# Sheet5.net
KiCad netlist of a schematic drawn in Altium Designer
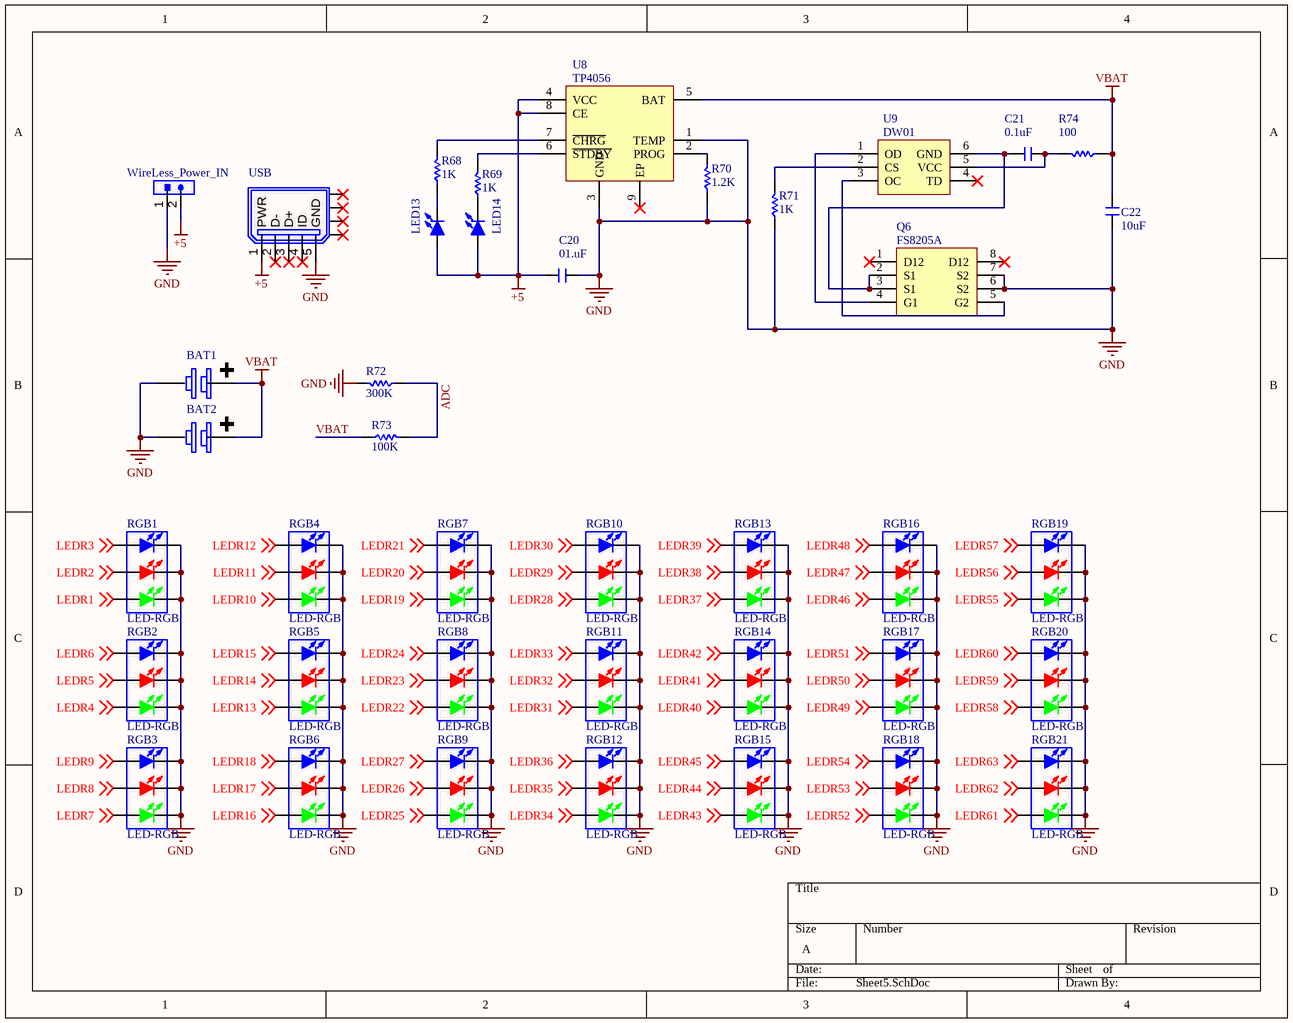
[diagram p0: Sheet5.SchDoc]

(export (version "E")
  (design (tool "Eeschema 10.0.6"))
  (components
    (comp (ref "BAT1")
      (value "Battery 1850")
      (footprint "18650 SINGLE 2")
      (libsource (lib "Battery Holder") (part "Battery 1850"))
    )
    (comp (ref "BAT2")
      (value "Battery 1850")
      (footprint "18650 SINGLE 2")
      (libsource (lib "Battery Holder") (part "Battery 1850"))
    )
    (comp (ref "C20")
      (value "01.uF")
      (footprint "C 0402")
      (description "Non-polar patch capacitor")
      (fields (field (name "版权归属") "源创客"))
      (libsource (lib "Passive (Resistor-Capacitor-Inductor-Veristor-Ferrite)") (part "C"))
    )
    (comp (ref "C21")
      (value "0.1uF")
      (footprint "C 0402")
      (description "Non-polar patch capacitor")
      (fields (field (name "版权归属") "源创客"))
      (libsource (lib "Passive (Resistor-Capacitor-Inductor-Veristor-Ferrite)") (part "C"))
    )
    (comp (ref "C22")
      (value "10uF")
      (footprint "C 0603")
      (description "Non-polar patch capacitor")
      (fields (field (name "版权归属") "源创客"))
      (libsource (lib "Passive (Resistor-Capacitor-Inductor-Veristor-Ferrite)") (part "C"))
    )
    (comp (ref "LED13")
      (value "LED-SMD")
      (footprint "LED 0805R")
      (description "Patch LED")
      (fields (field (name "版权归属") "源创客"))
      (libsource (lib "LED") (part "LED-SMD"))
    )
    (comp (ref "LED14")
      (value "LED-SMD")
      (footprint "LED 0805G")
      (description "Patch LED")
      (fields (field (name "版权归属") "源创客"))
      (libsource (lib "LED") (part "LED-SMD"))
    )
    (comp (ref "Q6")
      (value "FS8205A")
      (footprint "SSOP8_L")
      (description "Dual N-Channel Enhancement Mode Power MOSFET")
      (libsource (lib "Integrated Circuit") (part "FS8205A"))
    )
    (comp (ref "R68")
      (value "1K")
      (footprint "R 0402")
      (description "Chip resistor")
      (fields (field (name "版权归属") "源创客"))
      (libsource (lib "Passive (Resistor-Capacitor-Inductor-Veristor-Ferrite)") (part "R"))
    )
    (comp (ref "R69")
      (value "1K")
      (footprint "R 0402")
      (description "Chip resistor")
      (fields (field (name "版权归属") "源创客"))
      (libsource (lib "Passive (Resistor-Capacitor-Inductor-Veristor-Ferrite)") (part "R"))
    )
    (comp (ref "R70")
      (value "1.2K")
      (footprint "R 0402")
      (description "Chip resistor")
      (fields (field (name "版权归属") "源创客"))
      (libsource (lib "Passive (Resistor-Capacitor-Inductor-Veristor-Ferrite)") (part "R"))
    )
    (comp (ref "R71")
      (value "1K")
      (footprint "R 0402")
      (description "Chip resistor")
      (fields (field (name "版权归属") "源创客"))
      (libsource (lib "Passive (Resistor-Capacitor-Inductor-Veristor-Ferrite)") (part "R"))
    )
    (comp (ref "R72")
      (value "300K")
      (footprint "R 0805")
      (description "Chip resistor")
      (fields (field (name "版权归属") "源创客"))
      (libsource (lib "Passive (Resistor-Capacitor-Inductor-Veristor-Ferrite)") (part "R"))
    )
    (comp (ref "R73")
      (value "100K")
      (footprint "R 0805")
      (description "Chip resistor")
      (fields (field (name "版权归属") "源创客"))
      (libsource (lib "Passive (Resistor-Capacitor-Inductor-Veristor-Ferrite)") (part "R"))
    )
    (comp (ref "R74")
      (value "100")
      (footprint "R 0402")
      (description "Chip resistor")
      (fields (field (name "版权归属") "源创客"))
      (libsource (lib "Passive (Resistor-Capacitor-Inductor-Veristor-Ferrite)") (part "R"))
    )
    (comp (ref "RGB1")
      (value "LED-RGB")
      (footprint "LED 5050")
      (description "Three primary color LED")
      (fields (field (name "版权归属") "源创客"))
      (libsource (lib "LED") (part "LED-RGB"))
    )
    (comp (ref "RGB2")
      (value "LED-RGB")
      (footprint "LED 5050")
      (description "Three primary color LED")
      (fields (field (name "版权归属") "源创客"))
      (libsource (lib "LED") (part "LED-RGB"))
    )
    (comp (ref "RGB3")
      (value "LED-RGB")
      (footprint "LED 5050")
      (description "Three primary color LED")
      (fields (field (name "版权归属") "源创客"))
      (libsource (lib "LED") (part "LED-RGB"))
    )
    (comp (ref "RGB4")
      (value "LED-RGB")
      (footprint "LED 5050")
      (description "Three primary color LED")
      (fields (field (name "版权归属") "源创客"))
      (libsource (lib "LED") (part "LED-RGB"))
    )
    (comp (ref "RGB5")
      (value "LED-RGB")
      (footprint "LED 5050")
      (description "Three primary color LED")
      (fields (field (name "版权归属") "源创客"))
      (libsource (lib "LED") (part "LED-RGB"))
    )
    (comp (ref "RGB6")
      (value "LED-RGB")
      (footprint "LED 5050")
      (description "Three primary color LED")
      (fields (field (name "版权归属") "源创客"))
      (libsource (lib "LED") (part "LED-RGB"))
    )
    (comp (ref "RGB7")
      (value "LED-RGB")
      (footprint "LED 5050")
      (description "Three primary color LED")
      (fields (field (name "版权归属") "源创客"))
      (libsource (lib "LED") (part "LED-RGB"))
    )
    (comp (ref "RGB8")
      (value "LED-RGB")
      (footprint "LED 5050")
      (description "Three primary color LED")
      (fields (field (name "版权归属") "源创客"))
      (libsource (lib "LED") (part "LED-RGB"))
    )
    (comp (ref "RGB9")
      (value "LED-RGB")
      (footprint "LED 5050")
      (description "Three primary color LED")
      (fields (field (name "版权归属") "源创客"))
      (libsource (lib "LED") (part "LED-RGB"))
    )
    (comp (ref "RGB10")
      (value "LED-RGB")
      (footprint "LED 5050")
      (description "Three primary color LED")
      (fields (field (name "版权归属") "源创客"))
      (libsource (lib "LED") (part "LED-RGB"))
    )
    (comp (ref "RGB11")
      (value "LED-RGB")
      (footprint "LED 5050")
      (description "Three primary color LED")
      (fields (field (name "版权归属") "源创客"))
      (libsource (lib "LED") (part "LED-RGB"))
    )
    (comp (ref "RGB12")
      (value "LED-RGB")
      (footprint "LED 5050")
      (description "Three primary color LED")
      (fields (field (name "版权归属") "源创客"))
      (libsource (lib "LED") (part "LED-RGB"))
    )
    (comp (ref "RGB13")
      (value "LED-RGB")
      (footprint "LED 5050")
      (description "Three primary color LED")
      (fields (field (name "版权归属") "源创客"))
      (libsource (lib "LED") (part "LED-RGB"))
    )
    (comp (ref "RGB14")
      (value "LED-RGB")
      (footprint "LED 5050")
      (description "Three primary color LED")
      (fields (field (name "版权归属") "源创客"))
      (libsource (lib "LED") (part "LED-RGB"))
    )
    (comp (ref "RGB15")
      (value "LED-RGB")
      (footprint "LED 5050")
      (description "Three primary color LED")
      (fields (field (name "版权归属") "源创客"))
      (libsource (lib "LED") (part "LED-RGB"))
    )
    (comp (ref "RGB16")
      (value "LED-RGB")
      (footprint "LED 5050")
      (description "Three primary color LED")
      (fields (field (name "版权归属") "源创客"))
      (libsource (lib "LED") (part "LED-RGB"))
    )
    (comp (ref "RGB17")
      (value "LED-RGB")
      (footprint "LED 5050")
      (description "Three primary color LED")
      (fields (field (name "版权归属") "源创客"))
      (libsource (lib "LED") (part "LED-RGB"))
    )
    (comp (ref "RGB18")
      (value "LED-RGB")
      (footprint "LED 5050")
      (description "Three primary color LED")
      (fields (field (name "版权归属") "源创客"))
      (libsource (lib "LED") (part "LED-RGB"))
    )
    (comp (ref "RGB19")
      (value "LED-RGB")
      (footprint "LED 5050")
      (description "Three primary color LED")
      (fields (field (name "版权归属") "源创客"))
      (libsource (lib "LED") (part "LED-RGB"))
    )
    (comp (ref "RGB20")
      (value "LED-RGB")
      (footprint "LED 5050")
      (description "Three primary color LED")
      (fields (field (name "版权归属") "源创客"))
      (libsource (lib "LED") (part "LED-RGB"))
    )
    (comp (ref "RGB21")
      (value "LED-RGB")
      (footprint "LED 5050")
      (description "Three primary color LED")
      (fields (field (name "版权归属") "源创客"))
      (libsource (lib "LED") (part "LED-RGB"))
    )
    (comp (ref "U8")
      (value "TP4056")
      (footprint "SOP8_M-EP")
      (description "Lithium battery charge management")
      (fields (field (name "版权归属") "源创客"))
      (libsource (lib "Integrated Circuit") (part "TP4056"))
    )
    (comp (ref "U9")
      (value "DW01")
      (footprint "SOT23-6M")
      (description "Lithium battery overcurrent protection IC")
      (fields (field (name "版权归属") "源创客"))
      (libsource (lib "Integrated Circuit") (part "DW01"))
    )
    (comp (ref "USB")
      (value "USB-5P")
      (footprint "USB-micro_B")
      (description "Micro & Mini USB female")
      (fields (field (name "版权归属") "源创客"))
      (libsource (lib "IO (Power-USB-Serial-VGA-RJ-Audio-Buzzer)") (part "USB-5P"))
    )
    (comp (ref "WireLess_Power_IN")
      (value "HDR-1X2")
      (footprint "XH2.54-2P")
      (description "2P Connector")
      (fields (field (name "版权归属") "源创客"))
      (libsource (lib "Connectors") (part "Header 2"))
    )
  )
  (nets
    (net (code "1") (name "+5") (class "Default")
      (node (ref "C20") (pin "2") (pinfunction "2_2") (pintype "passive"))
      (node (ref "LED13") (pin "1") (pinfunction "A_1") (pintype "passive"))
      (node (ref "LED14") (pin "1") (pinfunction "A_1") (pintype "passive"))
      (node (ref "U8") (pin "4") (pinfunction "VCC_4") (pintype "passive"))
      (node (ref "U8") (pin "8") (pinfunction "CE_8") (pintype "passive"))
      (node (ref "USB") (pin "1") (pinfunction "PWR_1") (pintype "power_in"))
      (node (ref "WireLess_Power_IN") (pin "2") (pintype "passive"))
    )
    (net (code "2") (name "/ADC") (class "Default")
      (node (ref "R72") (pin "1") (pinfunction "1_1") (pintype "passive"))
      (node (ref "R73") (pin "2") (pinfunction "2_2") (pintype "passive"))
    )
    (net (code "3") (name "GND") (class "Default")
      (node (ref "BAT1") (pin "2") (pinfunction "-_2") (pintype "passive"))
      (node (ref "BAT2") (pin "2") (pinfunction "-_2") (pintype "passive"))
      (node (ref "C20") (pin "1") (pinfunction "1_1") (pintype "passive"))
      (node (ref "C22") (pin "1") (pinfunction "1_1") (pintype "passive"))
      (node (ref "Q6") (pin "6") (pinfunction "S2_6") (pintype "passive"))
      (node (ref "Q6") (pin "7") (pinfunction "S2_7") (pintype "passive"))
      (node (ref "R70") (pin "1") (pinfunction "1_1") (pintype "passive"))
      (node (ref "R71") (pin "1") (pinfunction "1_1") (pintype "passive"))
      (node (ref "R72") (pin "2") (pinfunction "2_2") (pintype "passive"))
      (node (ref "RGB1") (pin "2") (pinfunction "BULE_K_2") (pintype "passive"))
      (node (ref "RGB1") (pin "4") (pinfunction "RED_K_4") (pintype "passive"))
      (node (ref "RGB1") (pin "6") (pinfunction "GREEN_K_6") (pintype "passive"))
      (node (ref "RGB10") (pin "2") (pinfunction "BULE_K_2") (pintype "passive"))
      (node (ref "RGB10") (pin "4") (pinfunction "RED_K_4") (pintype "passive"))
      (node (ref "RGB10") (pin "6") (pinfunction "GREEN_K_6") (pintype "passive"))
      (node (ref "RGB11") (pin "2") (pinfunction "BULE_K_2") (pintype "passive"))
      (node (ref "RGB11") (pin "4") (pinfunction "RED_K_4") (pintype "passive"))
      (node (ref "RGB11") (pin "6") (pinfunction "GREEN_K_6") (pintype "passive"))
      (node (ref "RGB12") (pin "2") (pinfunction "BULE_K_2") (pintype "passive"))
      (node (ref "RGB12") (pin "4") (pinfunction "RED_K_4") (pintype "passive"))
      (node (ref "RGB12") (pin "6") (pinfunction "GREEN_K_6") (pintype "passive"))
      (node (ref "RGB13") (pin "2") (pinfunction "BULE_K_2") (pintype "passive"))
      (node (ref "RGB13") (pin "4") (pinfunction "RED_K_4") (pintype "passive"))
      (node (ref "RGB13") (pin "6") (pinfunction "GREEN_K_6") (pintype "passive"))
      (node (ref "RGB14") (pin "2") (pinfunction "BULE_K_2") (pintype "passive"))
      (node (ref "RGB14") (pin "4") (pinfunction "RED_K_4") (pintype "passive"))
      (node (ref "RGB14") (pin "6") (pinfunction "GREEN_K_6") (pintype "passive"))
      (node (ref "RGB15") (pin "2") (pinfunction "BULE_K_2") (pintype "passive"))
      (node (ref "RGB15") (pin "4") (pinfunction "RED_K_4") (pintype "passive"))
      (node (ref "RGB15") (pin "6") (pinfunction "GREEN_K_6") (pintype "passive"))
      (node (ref "RGB16") (pin "2") (pinfunction "BULE_K_2") (pintype "passive"))
      (node (ref "RGB16") (pin "4") (pinfunction "RED_K_4") (pintype "passive"))
      (node (ref "RGB16") (pin "6") (pinfunction "GREEN_K_6") (pintype "passive"))
      (node (ref "RGB17") (pin "2") (pinfunction "BULE_K_2") (pintype "passive"))
      (node (ref "RGB17") (pin "4") (pinfunction "RED_K_4") (pintype "passive"))
      (node (ref "RGB17") (pin "6") (pinfunction "GREEN_K_6") (pintype "passive"))
      (node (ref "RGB18") (pin "2") (pinfunction "BULE_K_2") (pintype "passive"))
      (node (ref "RGB18") (pin "4") (pinfunction "RED_K_4") (pintype "passive"))
      (node (ref "RGB18") (pin "6") (pinfunction "GREEN_K_6") (pintype "passive"))
      (node (ref "RGB19") (pin "2") (pinfunction "BULE_K_2") (pintype "passive"))
      (node (ref "RGB19") (pin "4") (pinfunction "RED_K_4") (pintype "passive"))
      (node (ref "RGB19") (pin "6") (pinfunction "GREEN_K_6") (pintype "passive"))
      (node (ref "RGB2") (pin "2") (pinfunction "BULE_K_2") (pintype "passive"))
      (node (ref "RGB2") (pin "4") (pinfunction "RED_K_4") (pintype "passive"))
      (node (ref "RGB2") (pin "6") (pinfunction "GREEN_K_6") (pintype "passive"))
      (node (ref "RGB20") (pin "2") (pinfunction "BULE_K_2") (pintype "passive"))
      (node (ref "RGB20") (pin "4") (pinfunction "RED_K_4") (pintype "passive"))
      (node (ref "RGB20") (pin "6") (pinfunction "GREEN_K_6") (pintype "passive"))
      (node (ref "RGB21") (pin "2") (pinfunction "BULE_K_2") (pintype "passive"))
      (node (ref "RGB21") (pin "4") (pinfunction "RED_K_4") (pintype "passive"))
      (node (ref "RGB21") (pin "6") (pinfunction "GREEN_K_6") (pintype "passive"))
      (node (ref "RGB3") (pin "2") (pinfunction "BULE_K_2") (pintype "passive"))
      (node (ref "RGB3") (pin "4") (pinfunction "RED_K_4") (pintype "passive"))
      (node (ref "RGB3") (pin "6") (pinfunction "GREEN_K_6") (pintype "passive"))
      (node (ref "RGB4") (pin "2") (pinfunction "BULE_K_2") (pintype "passive"))
      (node (ref "RGB4") (pin "4") (pinfunction "RED_K_4") (pintype "passive"))
      (node (ref "RGB4") (pin "6") (pinfunction "GREEN_K_6") (pintype "passive"))
      (node (ref "RGB5") (pin "2") (pinfunction "BULE_K_2") (pintype "passive"))
      (node (ref "RGB5") (pin "4") (pinfunction "RED_K_4") (pintype "passive"))
      (node (ref "RGB5") (pin "6") (pinfunction "GREEN_K_6") (pintype "passive"))
      (node (ref "RGB6") (pin "2") (pinfunction "BULE_K_2") (pintype "passive"))
      (node (ref "RGB6") (pin "4") (pinfunction "RED_K_4") (pintype "passive"))
      (node (ref "RGB6") (pin "6") (pinfunction "GREEN_K_6") (pintype "passive"))
      (node (ref "RGB7") (pin "2") (pinfunction "BULE_K_2") (pintype "passive"))
      (node (ref "RGB7") (pin "4") (pinfunction "RED_K_4") (pintype "passive"))
      (node (ref "RGB7") (pin "6") (pinfunction "GREEN_K_6") (pintype "passive"))
      (node (ref "RGB8") (pin "2") (pinfunction "BULE_K_2") (pintype "passive"))
      (node (ref "RGB8") (pin "4") (pinfunction "RED_K_4") (pintype "passive"))
      (node (ref "RGB8") (pin "6") (pinfunction "GREEN_K_6") (pintype "passive"))
      (node (ref "RGB9") (pin "2") (pinfunction "BULE_K_2") (pintype "passive"))
      (node (ref "RGB9") (pin "4") (pinfunction "RED_K_4") (pintype "passive"))
      (node (ref "RGB9") (pin "6") (pinfunction "GREEN_K_6") (pintype "passive"))
      (node (ref "U8") (pin "1") (pinfunction "TEMP_1") (pintype "passive"))
      (node (ref "U8") (pin "3") (pinfunction "GND_3") (pintype "passive"))
      (node (ref "USB") (pin "5") (pinfunction "GND_5") (pintype "power_in"))
      (node (ref "WireLess_Power_IN") (pin "1") (pintype "passive"))
    )
    (net (code "4") (name "LEDR1") (class "Default")
      (node (ref "RGB1") (pin "5") (pinfunction "GREEN_A_5") (pintype "passive"))
    )
    (net (code "5") (name "LEDR2") (class "Default")
      (node (ref "RGB1") (pin "3") (pinfunction "RED_A_3") (pintype "passive"))
    )
    (net (code "6") (name "LEDR3") (class "Default")
      (node (ref "RGB1") (pin "1") (pinfunction "BULE_A_1") (pintype "passive"))
    )
    (net (code "7") (name "LEDR4") (class "Default")
      (node (ref "RGB2") (pin "5") (pinfunction "GREEN_A_5") (pintype "passive"))
    )
    (net (code "8") (name "LEDR5") (class "Default")
      (node (ref "RGB2") (pin "3") (pinfunction "RED_A_3") (pintype "passive"))
    )
    (net (code "9") (name "LEDR6") (class "Default")
      (node (ref "RGB2") (pin "1") (pinfunction "BULE_A_1") (pintype "passive"))
    )
    (net (code "10") (name "LEDR7") (class "Default")
      (node (ref "RGB3") (pin "5") (pinfunction "GREEN_A_5") (pintype "passive"))
    )
    (net (code "11") (name "LEDR8") (class "Default")
      (node (ref "RGB3") (pin "3") (pinfunction "RED_A_3") (pintype "passive"))
    )
    (net (code "12") (name "LEDR9") (class "Default")
      (node (ref "RGB3") (pin "1") (pinfunction "BULE_A_1") (pintype "passive"))
    )
    (net (code "13") (name "LEDR10") (class "Default")
      (node (ref "RGB4") (pin "5") (pinfunction "GREEN_A_5") (pintype "passive"))
    )
    (net (code "14") (name "LEDR11") (class "Default")
      (node (ref "RGB4") (pin "3") (pinfunction "RED_A_3") (pintype "passive"))
    )
    (net (code "15") (name "LEDR12") (class "Default")
      (node (ref "RGB4") (pin "1") (pinfunction "BULE_A_1") (pintype "passive"))
    )
    (net (code "16") (name "LEDR13") (class "Default")
      (node (ref "RGB5") (pin "5") (pinfunction "GREEN_A_5") (pintype "passive"))
    )
    (net (code "17") (name "LEDR14") (class "Default")
      (node (ref "RGB5") (pin "3") (pinfunction "RED_A_3") (pintype "passive"))
    )
    (net (code "18") (name "LEDR15") (class "Default")
      (node (ref "RGB5") (pin "1") (pinfunction "BULE_A_1") (pintype "passive"))
    )
    (net (code "19") (name "LEDR16") (class "Default")
      (node (ref "RGB6") (pin "5") (pinfunction "GREEN_A_5") (pintype "passive"))
    )
    (net (code "20") (name "LEDR17") (class "Default")
      (node (ref "RGB6") (pin "3") (pinfunction "RED_A_3") (pintype "passive"))
    )
    (net (code "21") (name "LEDR18") (class "Default")
      (node (ref "RGB6") (pin "1") (pinfunction "BULE_A_1") (pintype "passive"))
    )
    (net (code "22") (name "LEDR19") (class "Default")
      (node (ref "RGB7") (pin "5") (pinfunction "GREEN_A_5") (pintype "passive"))
    )
    (net (code "23") (name "LEDR20") (class "Default")
      (node (ref "RGB7") (pin "3") (pinfunction "RED_A_3") (pintype "passive"))
    )
    (net (code "24") (name "LEDR21") (class "Default")
      (node (ref "RGB7") (pin "1") (pinfunction "BULE_A_1") (pintype "passive"))
    )
    (net (code "25") (name "LEDR22") (class "Default")
      (node (ref "RGB8") (pin "5") (pinfunction "GREEN_A_5") (pintype "passive"))
    )
    (net (code "26") (name "LEDR23") (class "Default")
      (node (ref "RGB8") (pin "3") (pinfunction "RED_A_3") (pintype "passive"))
    )
    (net (code "27") (name "LEDR24") (class "Default")
      (node (ref "RGB8") (pin "1") (pinfunction "BULE_A_1") (pintype "passive"))
    )
    (net (code "28") (name "LEDR25") (class "Default")
      (node (ref "RGB9") (pin "5") (pinfunction "GREEN_A_5") (pintype "passive"))
    )
    (net (code "29") (name "LEDR26") (class "Default")
      (node (ref "RGB9") (pin "3") (pinfunction "RED_A_3") (pintype "passive"))
    )
    (net (code "30") (name "LEDR27") (class "Default")
      (node (ref "RGB9") (pin "1") (pinfunction "BULE_A_1") (pintype "passive"))
    )
    (net (code "31") (name "LEDR28") (class "Default")
      (node (ref "RGB10") (pin "5") (pinfunction "GREEN_A_5") (pintype "passive"))
    )
    (net (code "32") (name "LEDR29") (class "Default")
      (node (ref "RGB10") (pin "3") (pinfunction "RED_A_3") (pintype "passive"))
    )
    (net (code "33") (name "LEDR30") (class "Default")
      (node (ref "RGB10") (pin "1") (pinfunction "BULE_A_1") (pintype "passive"))
    )
    (net (code "34") (name "LEDR31") (class "Default")
      (node (ref "RGB11") (pin "5") (pinfunction "GREEN_A_5") (pintype "passive"))
    )
    (net (code "35") (name "LEDR32") (class "Default")
      (node (ref "RGB11") (pin "3") (pinfunction "RED_A_3") (pintype "passive"))
    )
    (net (code "36") (name "LEDR33") (class "Default")
      (node (ref "RGB11") (pin "1") (pinfunction "BULE_A_1") (pintype "passive"))
    )
    (net (code "37") (name "LEDR34") (class "Default")
      (node (ref "RGB12") (pin "5") (pinfunction "GREEN_A_5") (pintype "passive"))
    )
    (net (code "38") (name "LEDR35") (class "Default")
      (node (ref "RGB12") (pin "3") (pinfunction "RED_A_3") (pintype "passive"))
    )
    (net (code "39") (name "LEDR36") (class "Default")
      (node (ref "RGB12") (pin "1") (pinfunction "BULE_A_1") (pintype "passive"))
    )
    (net (code "40") (name "LEDR37") (class "Default")
      (node (ref "RGB13") (pin "5") (pinfunction "GREEN_A_5") (pintype "passive"))
    )
    (net (code "41") (name "LEDR38") (class "Default")
      (node (ref "RGB13") (pin "3") (pinfunction "RED_A_3") (pintype "passive"))
    )
    (net (code "42") (name "LEDR39") (class "Default")
      (node (ref "RGB13") (pin "1") (pinfunction "BULE_A_1") (pintype "passive"))
    )
    (net (code "43") (name "LEDR40") (class "Default")
      (node (ref "RGB14") (pin "5") (pinfunction "GREEN_A_5") (pintype "passive"))
    )
    (net (code "44") (name "LEDR41") (class "Default")
      (node (ref "RGB14") (pin "3") (pinfunction "RED_A_3") (pintype "passive"))
    )
    (net (code "45") (name "LEDR42") (class "Default")
      (node (ref "RGB14") (pin "1") (pinfunction "BULE_A_1") (pintype "passive"))
    )
    (net (code "46") (name "LEDR43") (class "Default")
      (node (ref "RGB15") (pin "5") (pinfunction "GREEN_A_5") (pintype "passive"))
    )
    (net (code "47") (name "LEDR44") (class "Default")
      (node (ref "RGB15") (pin "3") (pinfunction "RED_A_3") (pintype "passive"))
    )
    (net (code "48") (name "LEDR45") (class "Default")
      (node (ref "RGB15") (pin "1") (pinfunction "BULE_A_1") (pintype "passive"))
    )
    (net (code "49") (name "LEDR46") (class "Default")
      (node (ref "RGB16") (pin "5") (pinfunction "GREEN_A_5") (pintype "passive"))
    )
    (net (code "50") (name "LEDR47") (class "Default")
      (node (ref "RGB16") (pin "3") (pinfunction "RED_A_3") (pintype "passive"))
    )
    (net (code "51") (name "LEDR48") (class "Default")
      (node (ref "RGB16") (pin "1") (pinfunction "BULE_A_1") (pintype "passive"))
    )
    (net (code "52") (name "LEDR49") (class "Default")
      (node (ref "RGB17") (pin "5") (pinfunction "GREEN_A_5") (pintype "passive"))
    )
    (net (code "53") (name "LEDR50") (class "Default")
      (node (ref "RGB17") (pin "3") (pinfunction "RED_A_3") (pintype "passive"))
    )
    (net (code "54") (name "LEDR51") (class "Default")
      (node (ref "RGB17") (pin "1") (pinfunction "BULE_A_1") (pintype "passive"))
    )
    (net (code "55") (name "LEDR52") (class "Default")
      (node (ref "RGB18") (pin "5") (pinfunction "GREEN_A_5") (pintype "passive"))
    )
    (net (code "56") (name "LEDR53") (class "Default")
      (node (ref "RGB18") (pin "3") (pinfunction "RED_A_3") (pintype "passive"))
    )
    (net (code "57") (name "LEDR54") (class "Default")
      (node (ref "RGB18") (pin "1") (pinfunction "BULE_A_1") (pintype "passive"))
    )
    (net (code "58") (name "LEDR55") (class "Default")
      (node (ref "RGB19") (pin "5") (pinfunction "GREEN_A_5") (pintype "passive"))
    )
    (net (code "59") (name "LEDR56") (class "Default")
      (node (ref "RGB19") (pin "3") (pinfunction "RED_A_3") (pintype "passive"))
    )
    (net (code "60") (name "LEDR57") (class "Default")
      (node (ref "RGB19") (pin "1") (pinfunction "BULE_A_1") (pintype "passive"))
    )
    (net (code "61") (name "LEDR58") (class "Default")
      (node (ref "RGB20") (pin "5") (pinfunction "GREEN_A_5") (pintype "passive"))
    )
    (net (code "62") (name "LEDR59") (class "Default")
      (node (ref "RGB20") (pin "3") (pinfunction "RED_A_3") (pintype "passive"))
    )
    (net (code "63") (name "LEDR60") (class "Default")
      (node (ref "RGB20") (pin "1") (pinfunction "BULE_A_1") (pintype "passive"))
    )
    (net (code "64") (name "LEDR61") (class "Default")
      (node (ref "RGB21") (pin "5") (pinfunction "GREEN_A_5") (pintype "passive"))
    )
    (net (code "65") (name "LEDR62") (class "Default")
      (node (ref "RGB21") (pin "3") (pinfunction "RED_A_3") (pintype "passive"))
    )
    (net (code "66") (name "LEDR63") (class "Default")
      (node (ref "RGB21") (pin "1") (pinfunction "BULE_A_1") (pintype "passive"))
    )
    (net (code "67") (name "Net-(LED13-K)") (class "Default")
      (node (ref "LED13") (pin "2") (pinfunction "K_2") (pintype "passive"))
      (node (ref "R68") (pin "1") (pinfunction "1_1") (pintype "passive"))
    )
    (net (code "68") (name "Net-(LED14-K)") (class "Default")
      (node (ref "LED14") (pin "2") (pinfunction "K_2") (pintype "passive"))
      (node (ref "R69") (pin "1") (pinfunction "1_1") (pintype "passive"))
    )
    (net (code "69") (name "Net-(Q6-G1)") (class "Default")
      (node (ref "Q6") (pin "4") (pinfunction "G1_4") (pintype "passive"))
      (node (ref "U9") (pin "1") (pinfunction "OD_1") (pintype "passive"))
    )
    (net (code "70") (name "Net-(Q6-G2)") (class "Default")
      (node (ref "Q6") (pin "5") (pinfunction "G2_5") (pintype "passive"))
      (node (ref "U9") (pin "3") (pinfunction "OC_3") (pintype "passive"))
    )
    (net (code "71") (name "Net-(U8-PROG)") (class "Default")
      (node (ref "R70") (pin "2") (pinfunction "2_2") (pintype "passive"))
      (node (ref "U8") (pin "2") (pinfunction "PROG_2") (pintype "passive"))
    )
    (net (code "72") (name "Net-(U8-~{CHRG})") (class "Default")
      (node (ref "R68") (pin "2") (pinfunction "2_2") (pintype "passive"))
      (node (ref "U8") (pin "7") (pinfunction "~{CHRG}_7") (pintype "passive"))
    )
    (net (code "73") (name "Net-(U8-~{STDBY})") (class "Default")
      (node (ref "R69") (pin "2") (pinfunction "2_2") (pintype "passive"))
      (node (ref "U8") (pin "6") (pinfunction "~{STDBY}_6") (pintype "passive"))
    )
    (net (code "74") (name "Net-(U9-CS)") (class "Default")
      (node (ref "R71") (pin "2") (pinfunction "2_2") (pintype "passive"))
      (node (ref "U9") (pin "2") (pinfunction "CS_2") (pintype "passive"))
    )
    (net (code "75") (name "Net-(U9-GND)") (class "Default")
      (node (ref "C21") (pin "1") (pinfunction "1_1") (pintype "passive"))
      (node (ref "Q6") (pin "2") (pinfunction "S1_2") (pintype "passive"))
      (node (ref "Q6") (pin "3") (pinfunction "S1_3") (pintype "passive"))
      (node (ref "U9") (pin "6") (pinfunction "GND_6") (pintype "passive"))
    )
    (net (code "76") (name "Net-(U9-VCC)") (class "Default")
      (node (ref "C21") (pin "2") (pinfunction "2_2") (pintype "passive"))
      (node (ref "R74") (pin "2") (pinfunction "2_2") (pintype "passive"))
      (node (ref "U9") (pin "5") (pinfunction "VCC_5") (pintype "passive"))
    )
    (net (code "77") (name "VBAT") (class "Default")
      (node (ref "BAT1") (pin "1") (pinfunction "+_1") (pintype "passive"))
      (node (ref "BAT2") (pin "1") (pinfunction "+_1") (pintype "passive"))
      (node (ref "C22") (pin "2") (pinfunction "2_2") (pintype "passive"))
      (node (ref "R73") (pin "1") (pinfunction "1_1") (pintype "passive"))
      (node (ref "R74") (pin "1") (pinfunction "1_1") (pintype "passive"))
      (node (ref "U8") (pin "5") (pinfunction "BAT_5") (pintype "passive"))
    )
    (net (code "78") (name "unconnected-(Q6-D12-Pad1)") (class "Default")
      (node (ref "Q6") (pin "1") (pinfunction "D12_1") (pintype "passive+no_connect"))
    )
    (net (code "79") (name "unconnected-(Q6-D12-Pad8)") (class "Default")
      (node (ref "Q6") (pin "8") (pinfunction "D12_8") (pintype "passive+no_connect"))
    )
    (net (code "80") (name "unconnected-(U8-EP-Pad9)") (class "Default")
      (node (ref "U8") (pin "9") (pinfunction "EP_9") (pintype "passive+no_connect"))
    )
    (net (code "81") (name "unconnected-(U9-TD-Pad4)") (class "Default")
      (node (ref "U9") (pin "4") (pinfunction "TD_4") (pintype "passive+no_connect"))
    )
    (net (code "82") (name "unconnected-(USB-D+-Pad3)") (class "Default")
      (node (ref "USB") (pin "3") (pinfunction "D+_3") (pintype "tri_state+no_connect"))
    )
    (net (code "83") (name "unconnected-(USB-D--Pad2)") (class "Default")
      (node (ref "USB") (pin "2") (pinfunction "D-_2") (pintype "tri_state+no_connect"))
    )
    (net (code "84") (name "unconnected-(USB-ID-Pad4)") (class "Default")
      (node (ref "USB") (pin "4") (pinfunction "ID_4") (pintype "passive+no_connect"))
    )
    (net (code "85") (name "unconnected-(USB-SHIELD-Pad5)") (class "Default")
      (node (ref "USB") (pin "5") (pinfunction "SHIELD_5") (pintype "passive+no_connect"))
    )
    (net (code "86") (name "unconnected-(USB-SHIELD-Pad5)_1") (class "Default")
      (node (ref "USB") (pin "5") (pinfunction "SHIELD_5") (pintype "passive+no_connect"))
    )
    (net (code "87") (name "unconnected-(USB-SHIELD-Pad5)_2") (class "Default")
      (node (ref "USB") (pin "5") (pinfunction "SHIELD_5") (pintype "passive+no_connect"))
    )
    (net (code "88") (name "unconnected-(USB-SHIELD-Pad5)_3") (class "Default")
      (node (ref "USB") (pin "5") (pinfunction "SHIELD_5") (pintype "passive+no_connect"))
    )
  )
)
